# soil_moisture_meter.net
KiCad netlist of a schematic drawn in EAGLE
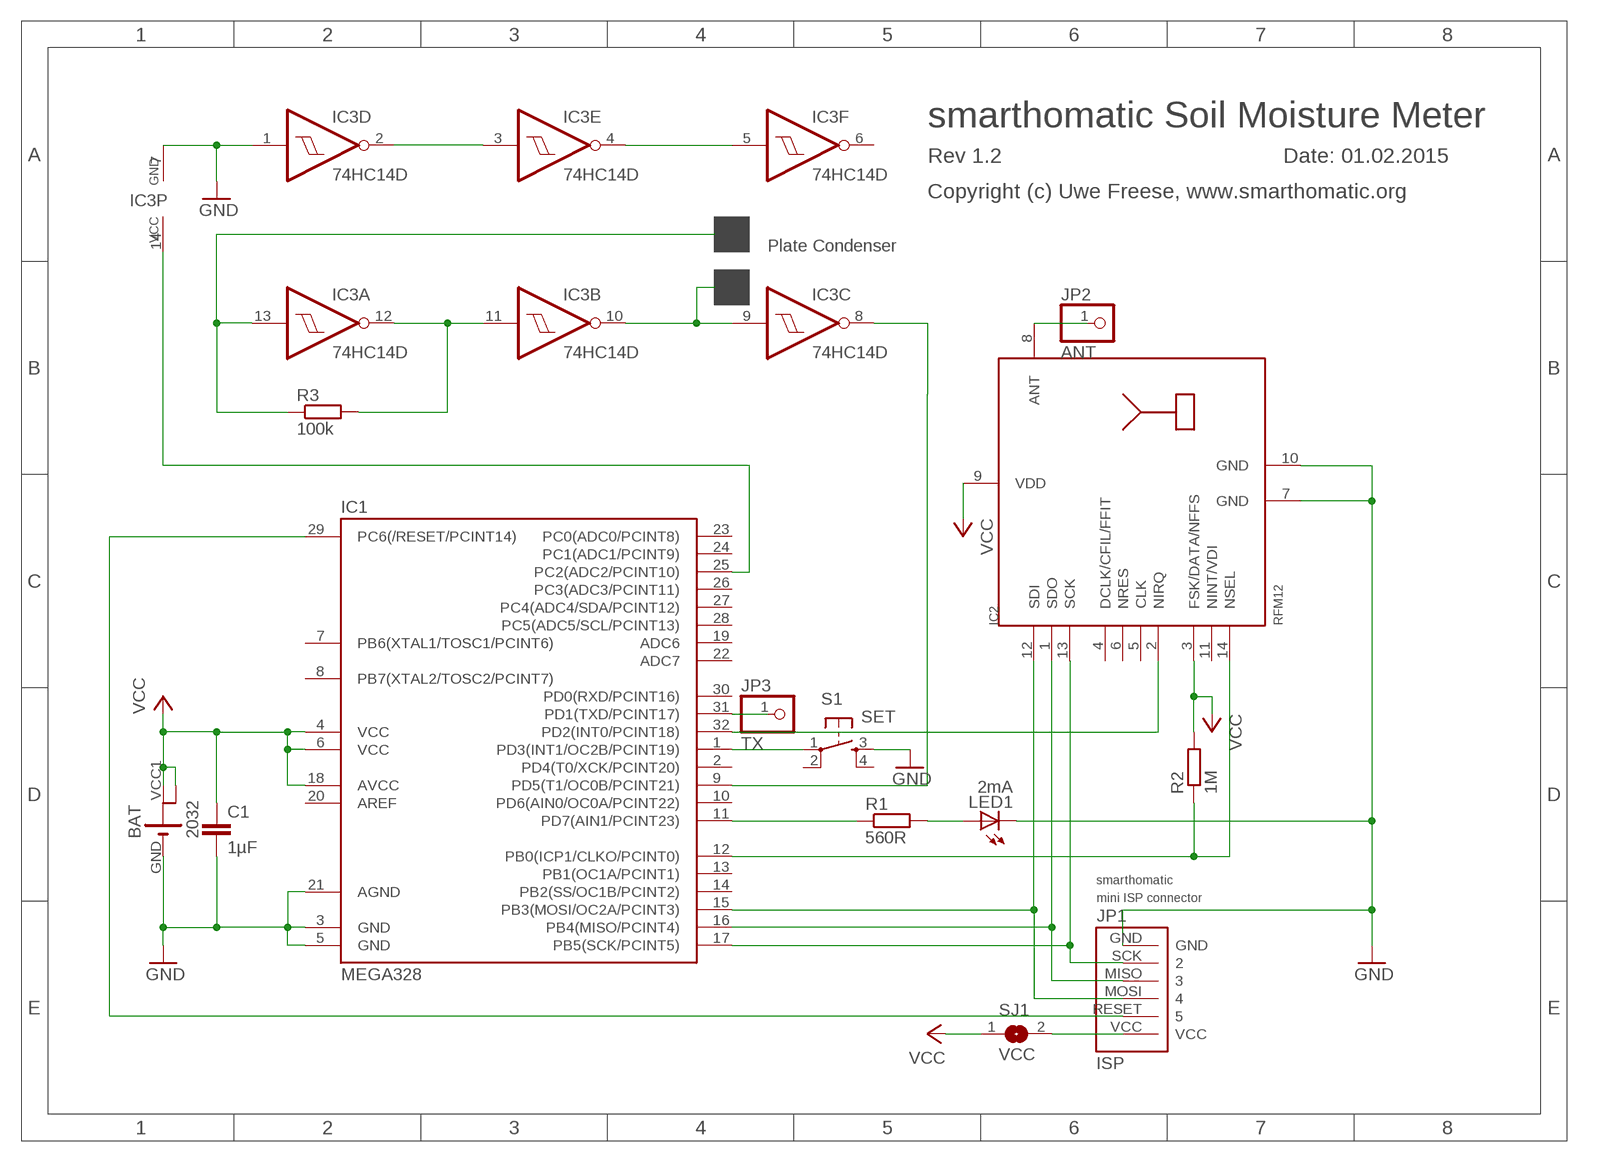
[diagram p0: schematic, sheet 1]

(export (version "E")
  (design (tool "Eeschema 10.0.6"))
  (components
    (comp (ref "BAT")
      (value "2032")
      (footprint "eagle-import:KZH20SMD")
      (libsource (lib "eagle-import") (part "2032"))
    )
    (comp (ref "C1")
      (value "1µF")
      (footprint "eagle-import:C0603")
      (libsource (lib "eagle-import") (part "C-EUC0603"))
    )
    (comp (ref "IC1")
      (value "MEGA328")
      (footprint "eagle-import:TQFP32-08")
      (libsource (lib "eagle-import") (part "MEGA48/88/168-AU"))
    )
    (comp (ref "IC2")
      (value "RFM12")
      (footprint "eagle-import:RFM")
      (libsource (lib "eagle-import") (part "RFM12"))
    )
    (comp (ref "IC3")
      (value "74HC14D")
      (footprint "eagle-import:SO14")
      (libsource (lib "eagle-import") (part "7414DHC"))
    )
    (comp (ref "JP1")
      (value "ISP")
      (footprint "eagle-import:PINHD_1X6_1.27")
      (libsource (lib "eagle-import") (part "SHC_MINI_ISPP"))
    )
    (comp (ref "JP2")
      (value "ANT")
      (footprint "eagle-import:1X01")
      (libsource (lib "eagle-import") (part "PINHD-1X1"))
    )
    (comp (ref "JP3")
      (value "TX")
      (footprint "eagle-import:1X01")
      (libsource (lib "eagle-import") (part "PINHD-1X1"))
    )
    (comp (ref "LED1")
      (value "2mA")
      (footprint "eagle-import:LED3MM")
      (libsource (lib "eagle-import") (part "LED3MM"))
    )
    (comp (ref "R1")
      (value "560R")
      (footprint "eagle-import:R0603")
      (libsource (lib "eagle-import") (part "R-EU_R0603"))
    )
    (comp (ref "R2")
      (value "1M")
      (footprint "eagle-import:R0603")
      (libsource (lib "eagle-import") (part "R-EU_R0603"))
    )
    (comp (ref "R3")
      (value "100k")
      (footprint "eagle-import:R0603")
      (libsource (lib "eagle-import") (part "R-EU_R0603"))
    )
    (comp (ref "S1")
      (value "SET")
      (footprint "eagle-import:SCHURTER_LSG")
      (libsource (lib "eagle-import") (part "LSG"))
    )
    (comp (ref "SJ1")
      (value "VCC")
      (footprint "eagle-import:SJ")
      (libsource (lib "eagle-import") (part "SJ"))
    )
  )
  (nets
    (net (code "1") (name "GND") (class "Default")
      (node (ref "BAT") (pin "GND") (pinfunction "GND_GND") (pintype "power_in"))
      (node (ref "C1") (pin "2") (pinfunction "2_2") (pintype "passive"))
      (node (ref "IC1") (pin "21") (pinfunction "AGND_21") (pintype "power_in"))
      (node (ref "IC1") (pin "3") (pinfunction "GND_3") (pintype "power_in"))
      (node (ref "IC1") (pin "5") (pinfunction "GND_5") (pintype "power_in"))
      (node (ref "IC2") (pin "10") (pinfunction "GND_10") (pintype "power_in"))
      (node (ref "IC2") (pin "7") (pinfunction "GND_7") (pintype "power_in"))
      (node (ref "IC3") (pin "1") (pinfunction "I_1") (pintype "input"))
      (node (ref "IC3") (pin "7") (pinfunction "GND_7") (pintype "power_in"))
      (node (ref "JP1") (pin "GND") (pinfunction "GND_GND") (pintype "power_in"))
      (node (ref "LED1") (pin "K") (pinfunction "C_K") (pintype "passive"))
      (node (ref "S1") (pin "3") (pinfunction "S_3") (pintype "passive"))
    )
    (net (code "2") (name "Net-(IC1-PB0(ICP1{slash}CLKO{slash}PCINT0))") (class "Default")
      (node (ref "IC1") (pin "12") (pinfunction "PB0(ICP1/CLKO/PCINT0)_12") (pintype "bidirectional"))
      (node (ref "IC2") (pin "14") (pinfunction "NSEL_14") (pintype "bidirectional"))
      (node (ref "R2") (pin "1") (pinfunction "1_1") (pintype "passive"))
    )
    (net (code "3") (name "Net-(IC1-PB3(MOSI{slash}OC2A{slash}PCINT3))") (class "Default")
      (node (ref "IC1") (pin "15") (pinfunction "PB3(MOSI/OC2A/PCINT3)_15") (pintype "bidirectional"))
      (node (ref "IC2") (pin "12") (pinfunction "SDI_12") (pintype "bidirectional"))
      (node (ref "JP1") (pin "MOSI") (pinfunction "4_MOSI") (pintype "output"))
    )
    (net (code "4") (name "Net-(IC1-PB4(MISO{slash}PCINT4))") (class "Default")
      (node (ref "IC1") (pin "16") (pinfunction "PB4(MISO/PCINT4)_16") (pintype "bidirectional"))
      (node (ref "IC2") (pin "1") (pinfunction "SDO_1") (pintype "bidirectional"))
      (node (ref "JP1") (pin "MISO") (pinfunction "3_MISO") (pintype "bidirectional"))
    )
    (net (code "5") (name "Net-(IC1-PB5(SCK{slash}PCINT5))") (class "Default")
      (node (ref "IC1") (pin "17") (pinfunction "PB5(SCK/PCINT5)_17") (pintype "bidirectional"))
      (node (ref "IC2") (pin "13") (pinfunction "SCK_13") (pintype "bidirectional"))
      (node (ref "JP1") (pin "SCK") (pinfunction "2_SCK") (pintype "output"))
    )
    (net (code "6") (name "Net-(IC1-PC2(ADC2{slash}PCINT10))") (class "Default")
      (node (ref "IC1") (pin "25") (pinfunction "PC2(ADC2/PCINT10)_25") (pintype "bidirectional"))
      (node (ref "IC3") (pin "14") (pinfunction "VCC_14") (pintype "power_in"))
    )
    (net (code "7") (name "Net-(IC1-PC6({slash}RESET{slash}PCINT14))") (class "Default")
      (node (ref "IC1") (pin "29") (pinfunction "PC6(/RESET/PCINT14)_29") (pintype "bidirectional"))
      (node (ref "JP1") (pin "RESET") (pinfunction "5_RESET") (pintype "output"))
    )
    (net (code "8") (name "Net-(IC1-PD1(TXD{slash}PCINT17))") (class "Default")
      (node (ref "IC1") (pin "31") (pinfunction "PD1(TXD/PCINT17)_31") (pintype "bidirectional"))
      (node (ref "JP3") (pin "1") (pinfunction "1_1") (pintype "passive"))
    )
    (net (code "9") (name "Net-(IC1-PD2(INT0{slash}PCINT18))") (class "Default")
      (node (ref "IC1") (pin "32") (pinfunction "PD2(INT0/PCINT18)_32") (pintype "bidirectional"))
      (node (ref "IC2") (pin "2") (pinfunction "NIRQ_2") (pintype "bidirectional"))
    )
    (net (code "10") (name "Net-(IC1-PD3(INT1{slash}OC2B{slash}PCINT19))") (class "Default")
      (node (ref "IC1") (pin "1") (pinfunction "PD3(INT1/OC2B/PCINT19)_1") (pintype "bidirectional"))
      (node (ref "S1") (pin "1") (pinfunction "P_1") (pintype "passive"))
    )
    (net (code "11") (name "Net-(IC1-PD5(T1{slash}OC0B{slash}PCINT21))") (class "Default")
      (node (ref "IC1") (pin "9") (pinfunction "PD5(T1/OC0B/PCINT21)_9") (pintype "bidirectional"))
      (node (ref "IC3") (pin "8") (pinfunction "O_8") (pintype "output"))
    )
    (net (code "12") (name "Net-(IC1-PD7(AIN1{slash}PCINT23))") (class "Default")
      (node (ref "IC1") (pin "11") (pinfunction "PD7(AIN1/PCINT23)_11") (pintype "bidirectional"))
      (node (ref "R1") (pin "1") (pinfunction "1_1") (pintype "passive"))
    )
    (net (code "13") (name "Net-(IC2-ANT)") (class "Default")
      (node (ref "IC2") (pin "8") (pinfunction "ANT_8") (pintype "output"))
      (node (ref "JP2") (pin "1") (pinfunction "1_1") (pintype "passive"))
    )
    (net (code "14") (name "Net-(IC3A-I)") (class "Default")
      (node (ref "IC3") (pin "13") (pinfunction "I_13") (pintype "input"))
      (node (ref "R3") (pin "1") (pinfunction "1_1") (pintype "passive"))
    )
    (net (code "15") (name "Net-(IC3A-O)") (class "Default")
      (node (ref "IC3") (pin "11") (pinfunction "I_11") (pintype "input"))
      (node (ref "IC3") (pin "12") (pinfunction "O_12") (pintype "output"))
      (node (ref "R3") (pin "2") (pinfunction "2_2") (pintype "passive"))
    )
    (net (code "16") (name "Net-(IC3B-O)") (class "Default")
      (node (ref "IC3") (pin "10") (pinfunction "O_10") (pintype "output"))
      (node (ref "IC3") (pin "9") (pinfunction "I_9") (pintype "input"))
    )
    (net (code "17") (name "Net-(IC3D-O)") (class "Default")
      (node (ref "IC3") (pin "2") (pinfunction "O_2") (pintype "output"))
      (node (ref "IC3") (pin "3") (pinfunction "I_3") (pintype "input"))
    )
    (net (code "18") (name "Net-(IC3E-O)") (class "Default")
      (node (ref "IC3") (pin "4") (pinfunction "O_4") (pintype "output"))
      (node (ref "IC3") (pin "5") (pinfunction "I_5") (pintype "input"))
    )
    (net (code "19") (name "Net-(JP1-PadVCC)") (class "Default")
      (node (ref "JP1") (pin "VCC") (pinfunction "VCC_VCC") (pintype "power_in"))
      (node (ref "SJ1") (pin "2") (pinfunction "2_2") (pintype "passive"))
    )
    (net (code "20") (name "Net-(LED1-PadA)") (class "Default")
      (node (ref "LED1") (pin "A") (pinfunction "A_A") (pintype "passive"))
      (node (ref "R1") (pin "2") (pinfunction "2_2") (pintype "passive"))
    )
    (net (code "21") (name "VCC") (class "Default")
      (node (ref "BAT") (pin "VCC1") (pinfunction "VCC1_VCC1") (pintype "power_in"))
      (node (ref "BAT") (pin "VCC2") (pinfunction "VCC2_VCC2") (pintype "power_in"))
      (node (ref "C1") (pin "1") (pinfunction "1_1") (pintype "passive"))
      (node (ref "IC1") (pin "18") (pinfunction "AVCC_18") (pintype "passive"))
      (node (ref "IC1") (pin "4") (pinfunction "VCC_4") (pintype "power_in"))
      (node (ref "IC1") (pin "6") (pinfunction "VCC_6") (pintype "power_in"))
      (node (ref "IC2") (pin "3") (pinfunction "FSK/DATA/NFFS_3") (pintype "bidirectional"))
      (node (ref "IC2") (pin "9") (pinfunction "VDD_9") (pintype "power_in"))
      (node (ref "R2") (pin "2") (pinfunction "2_2") (pintype "passive"))
      (node (ref "SJ1") (pin "1") (pinfunction "1_1") (pintype "passive"))
    )
    (net (code "22") (name "unconnected-(IC1-ADC6-Pad19)") (class "Default")
      (node (ref "IC1") (pin "19") (pinfunction "ADC6_19") (pintype "passive"))
    )
    (net (code "23") (name "unconnected-(IC1-ADC7-Pad22)") (class "Default")
      (node (ref "IC1") (pin "22") (pinfunction "ADC7_22") (pintype "passive"))
    )
    (net (code "24") (name "unconnected-(IC1-AREF-Pad20)") (class "Default")
      (node (ref "IC1") (pin "20") (pinfunction "AREF_20") (pintype "passive"))
    )
    (net (code "25") (name "unconnected-(IC1-PB1(OC1A{slash}PCINT1)-Pad13)") (class "Default")
      (node (ref "IC1") (pin "13") (pinfunction "PB1(OC1A/PCINT1)_13") (pintype "bidirectional"))
    )
    (net (code "26") (name "unconnected-(IC1-PB2(SS{slash}OC1B{slash}PCINT2)-Pad14)") (class "Default")
      (node (ref "IC1") (pin "14") (pinfunction "PB2(SS/OC1B/PCINT2)_14") (pintype "bidirectional"))
    )
    (net (code "27") (name "unconnected-(IC1-PB6(XTAL1{slash}TOSC1{slash}PCINT6)-Pad7)") (class "Default")
      (node (ref "IC1") (pin "7") (pinfunction "PB6(XTAL1/TOSC1/PCINT6)_7") (pintype "bidirectional"))
    )
    (net (code "28") (name "unconnected-(IC1-PB7(XTAL2{slash}TOSC2{slash}PCINT7)-Pad8)") (class "Default")
      (node (ref "IC1") (pin "8") (pinfunction "PB7(XTAL2/TOSC2/PCINT7)_8") (pintype "bidirectional"))
    )
    (net (code "29") (name "unconnected-(IC1-PC0(ADC0{slash}PCINT8)-Pad23)") (class "Default")
      (node (ref "IC1") (pin "23") (pinfunction "PC0(ADC0/PCINT8)_23") (pintype "bidirectional"))
    )
    (net (code "30") (name "unconnected-(IC1-PC1(ADC1{slash}PCINT9)-Pad24)") (class "Default")
      (node (ref "IC1") (pin "24") (pinfunction "PC1(ADC1/PCINT9)_24") (pintype "bidirectional"))
    )
    (net (code "31") (name "unconnected-(IC1-PC3(ADC3{slash}PCINT11)-Pad26)") (class "Default")
      (node (ref "IC1") (pin "26") (pinfunction "PC3(ADC3/PCINT11)_26") (pintype "bidirectional"))
    )
    (net (code "32") (name "unconnected-(IC1-PC4(ADC4{slash}SDA{slash}PCINT12)-Pad27)") (class "Default")
      (node (ref "IC1") (pin "27") (pinfunction "PC4(ADC4/SDA/PCINT12)_27") (pintype "bidirectional"))
    )
    (net (code "33") (name "unconnected-(IC1-PC5(ADC5{slash}SCL{slash}PCINT13)-Pad28)") (class "Default")
      (node (ref "IC1") (pin "28") (pinfunction "PC5(ADC5/SCL/PCINT13)_28") (pintype "bidirectional"))
    )
    (net (code "34") (name "unconnected-(IC1-PD0(RXD{slash}PCINT16)-Pad30)") (class "Default")
      (node (ref "IC1") (pin "30") (pinfunction "PD0(RXD/PCINT16)_30") (pintype "bidirectional"))
    )
    (net (code "35") (name "unconnected-(IC1-PD4(T0{slash}XCK{slash}PCINT20)-Pad2)") (class "Default")
      (node (ref "IC1") (pin "2") (pinfunction "PD4(T0/XCK/PCINT20)_2") (pintype "bidirectional"))
    )
    (net (code "36") (name "unconnected-(IC1-PD6(AIN0{slash}OC0A{slash}PCINT22)-Pad10)") (class "Default")
      (node (ref "IC1") (pin "10") (pinfunction "PD6(AIN0/OC0A/PCINT22)_10") (pintype "bidirectional"))
    )
    (net (code "37") (name "unconnected-(IC2-CLK-Pad5)") (class "Default")
      (node (ref "IC2") (pin "5") (pinfunction "CLK_5") (pintype "bidirectional"))
    )
    (net (code "38") (name "unconnected-(IC2-DCLK{slash}CFIL{slash}FFIT-Pad4)") (class "Default")
      (node (ref "IC2") (pin "4") (pinfunction "DCLK/CFIL/FFIT_4") (pintype "bidirectional"))
    )
    (net (code "39") (name "unconnected-(IC2-NINT{slash}VDI-Pad11)") (class "Default")
      (node (ref "IC2") (pin "11") (pinfunction "NINT/VDI_11") (pintype "bidirectional"))
    )
    (net (code "40") (name "unconnected-(IC2-NRES-Pad6)") (class "Default")
      (node (ref "IC2") (pin "6") (pinfunction "NRES_6") (pintype "bidirectional"))
    )
    (net (code "41") (name "unconnected-(IC3F-O-Pad6)") (class "Default")
      (node (ref "IC3") (pin "6") (pinfunction "O_6") (pintype "output"))
    )
    (net (code "42") (name "unconnected-(S1-P1-Pad2)") (class "Default")
      (node (ref "S1") (pin "2") (pinfunction "P1_2") (pintype "passive"))
    )
    (net (code "43") (name "unconnected-(S1-S1-Pad4)") (class "Default")
      (node (ref "S1") (pin "4") (pinfunction "S1_4") (pintype "passive"))
    )
  )
)
